# etch.net
KiCad netlist of a schematic drawn in EAGLE
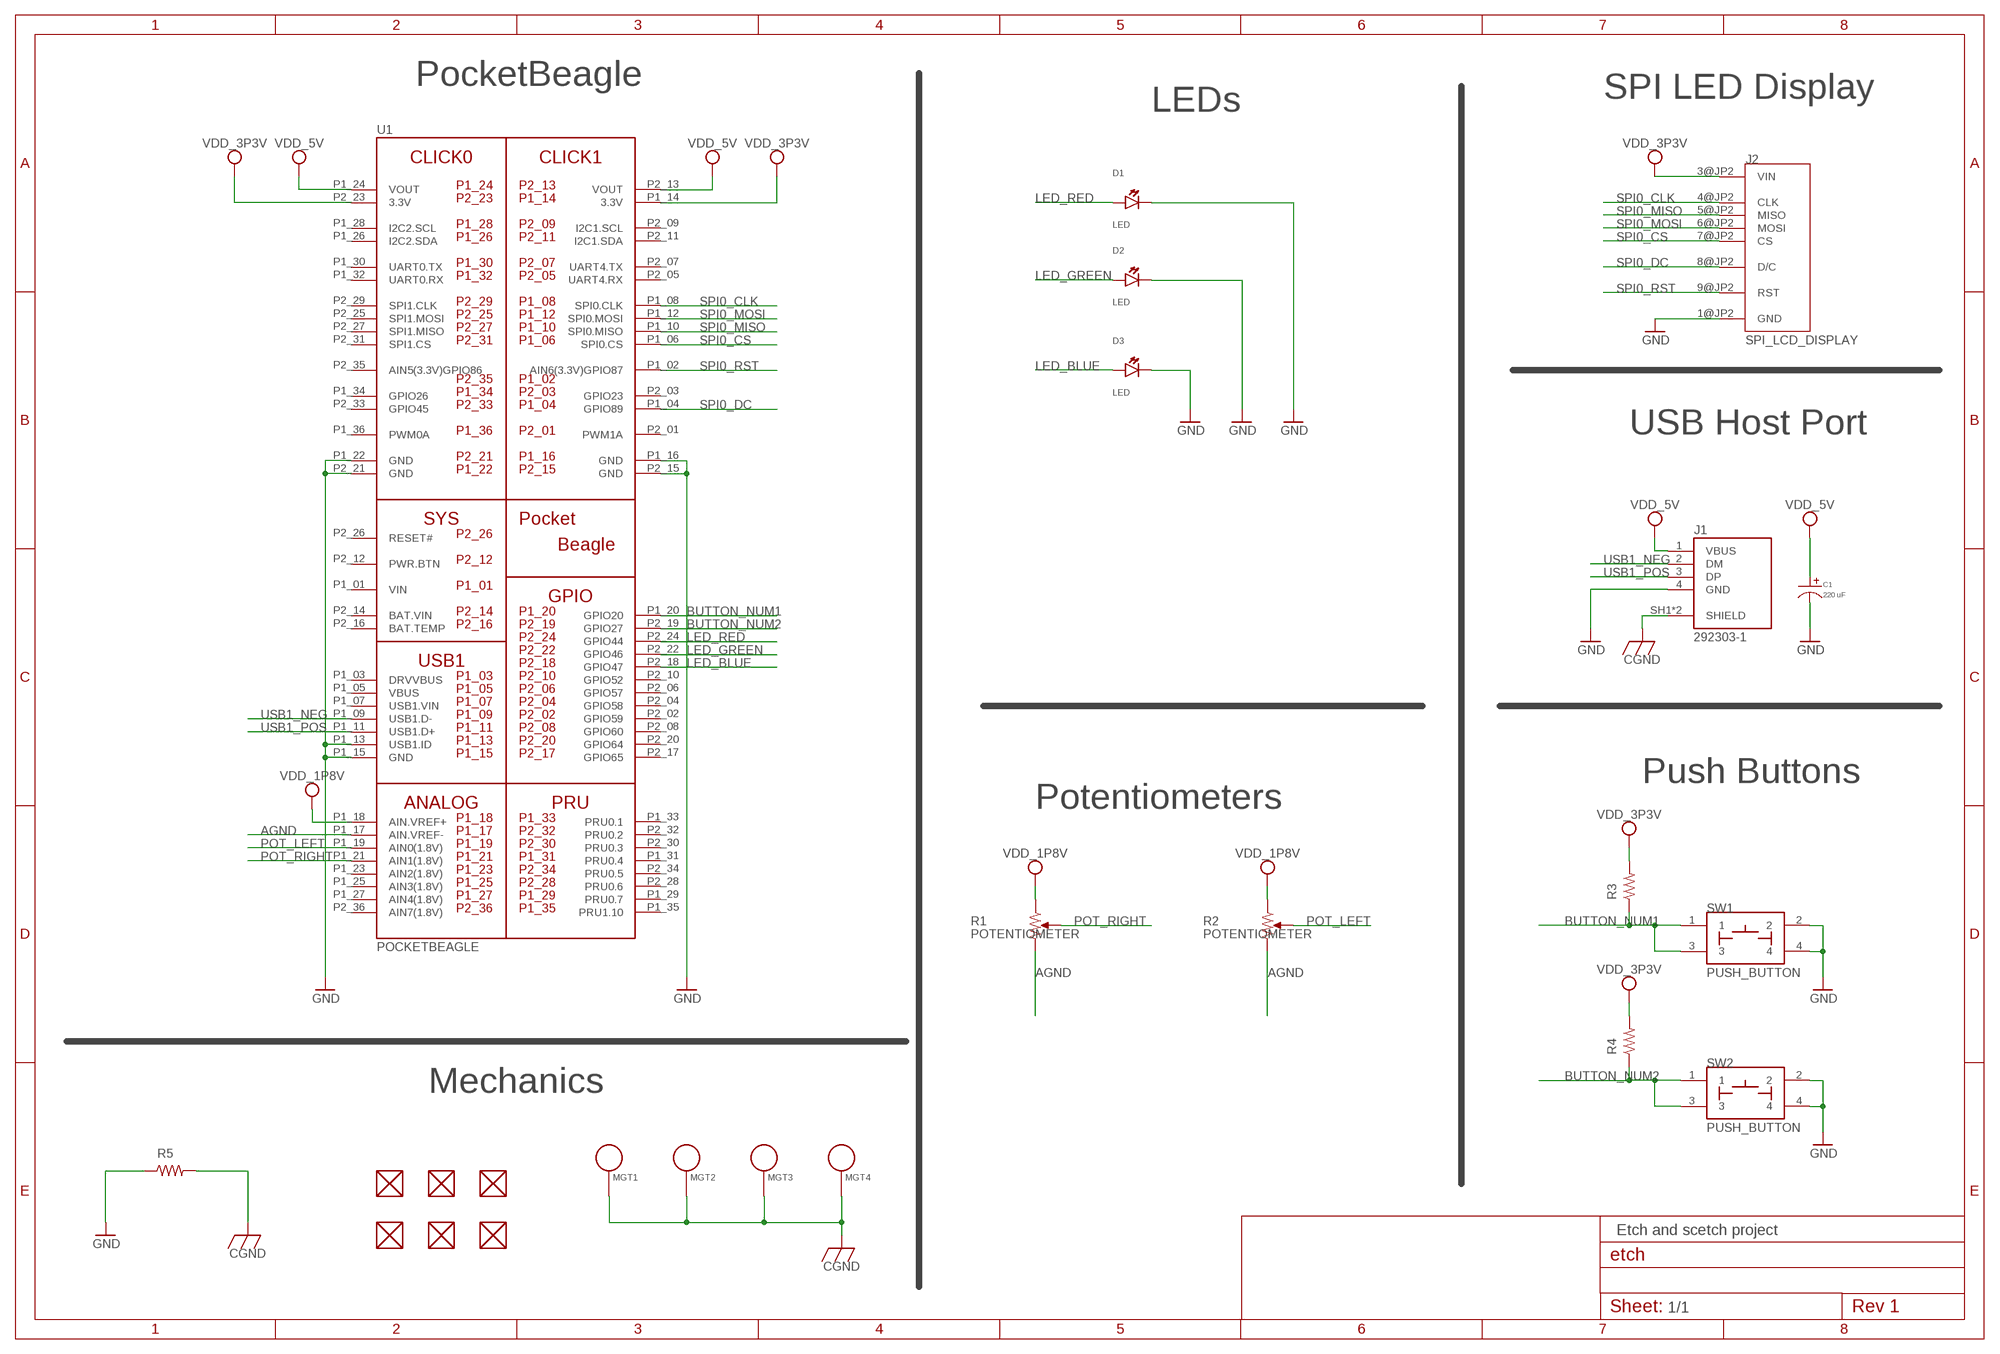
[diagram p0: schematic, sheet 1]

(export (version "E")
  (design (tool "Eeschema 10.0.6"))
  (components
    (comp (ref "C1")
      (value "220 uF")
      (footprint "eagle-import:CP10MM")
      (libsource (lib "eagle-import") (part "CAPACITOR_P_10MM"))
    )
    (comp (ref "D1")
      (value "LED")
      (footprint "eagle-import:EIA-STD")
      (libsource (lib "eagle-import") (part "LED"))
    )
    (comp (ref "D2")
      (value "LED")
      (footprint "eagle-import:EIA-STD")
      (libsource (lib "eagle-import") (part "LED"))
    )
    (comp (ref "D3")
      (value "LED")
      (footprint "eagle-import:EIA-STD")
      (libsource (lib "eagle-import") (part "LED"))
    )
    (comp (ref "FUD1")
      (value "FIDUCIAL")
      (footprint "eagle-import:FIDUCIAL_40MIL")
      (libsource (lib "eagle-import") (part "FIDUCIAL"))
    )
    (comp (ref "FUD2")
      (value "FIDUCIAL")
      (footprint "eagle-import:FIDUCIAL_40MIL")
      (libsource (lib "eagle-import") (part "FIDUCIAL"))
    )
    (comp (ref "FUD3")
      (value "FIDUCIAL")
      (footprint "eagle-import:FIDUCIAL_40MIL")
      (libsource (lib "eagle-import") (part "FIDUCIAL"))
    )
    (comp (ref "FUD4")
      (value "FIDUCIAL")
      (footprint "eagle-import:FIDUCIAL_40MIL")
      (libsource (lib "eagle-import") (part "FIDUCIAL"))
    )
    (comp (ref "FUD5")
      (value "FIDUCIAL")
      (footprint "eagle-import:FIDUCIAL_40MIL")
      (libsource (lib "eagle-import") (part "FIDUCIAL"))
    )
    (comp (ref "FUD6")
      (value "FIDUCIAL")
      (footprint "eagle-import:FIDUCIAL_40MIL")
      (libsource (lib "eagle-import") (part "FIDUCIAL"))
    )
    (comp (ref "J1")
      (value "292303-1")
      (footprint "eagle-import:TE_292303-1")
      (fields (field (name "MF") "TE Connectivity"))
      (libsource (lib "eagle-import") (part "292303-1"))
    )
    (comp (ref "J2")
      (value "SPI_LCD_DISPLAY")
      (footprint "eagle-import:TFT_LCD_PCB")
      (libsource (lib "eagle-import") (part "SPI_LCD_DISPLAY"))
    )
    (comp (ref "MGT1")
      (value "MOUNTING_HOLE")
      (footprint "eagle-import:MOUNTING_HOLE")
      (libsource (lib "eagle-import") (part "MOUNTING_HOLE"))
    )
    (comp (ref "MGT2")
      (value "MOUNTING_HOLE")
      (footprint "eagle-import:MOUNTING_HOLE")
      (libsource (lib "eagle-import") (part "MOUNTING_HOLE"))
    )
    (comp (ref "MGT3")
      (value "MOUNTING_HOLE")
      (footprint "eagle-import:MOUNTING_HOLE")
      (libsource (lib "eagle-import") (part "MOUNTING_HOLE"))
    )
    (comp (ref "MGT4")
      (value "MOUNTING_HOLE")
      (footprint "eagle-import:MOUNTING_HOLE")
      (libsource (lib "eagle-import") (part "MOUNTING_HOLE"))
    )
    (comp (ref "R1")
      (value "POTENTIOMETER")
      (footprint "eagle-import:POT-PO90S")
      (libsource (lib "eagle-import") (part "POTENTIOMETER"))
    )
    (comp (ref "R2")
      (value "POTENTIOMETER")
      (footprint "eagle-import:POT-PO90S")
      (libsource (lib "eagle-import") (part "POTENTIOMETER"))
    )
    (comp (ref "R3")
      (value "R_R0603")
      (footprint "eagle-import:R0603")
      (libsource (lib "eagle-import") (part "R_R0603"))
    )
    (comp (ref "R4")
      (value "R_R0603")
      (footprint "eagle-import:R0603")
      (libsource (lib "eagle-import") (part "R_R0603"))
    )
    (comp (ref "R5")
      (value "R_R0603")
      (footprint "eagle-import:R0603")
      (libsource (lib "eagle-import") (part "R_R0603"))
    )
    (comp (ref "SW1")
      (value "PUSH_BUTTON")
      (footprint "eagle-import:BUTTON_12.5MM")
      (libsource (lib "eagle-import") (part "PUSH_BUTTON"))
    )
    (comp (ref "SW2")
      (value "PUSH_BUTTON")
      (footprint "eagle-import:BUTTON_12.5MM")
      (libsource (lib "eagle-import") (part "PUSH_BUTTON"))
    )
    (comp (ref "U1")
      (value "POCKETBEAGLE")
      (footprint "eagle-import:POCKETBEAGLE")
      (libsource (lib "eagle-import") (part "POCKETBEAGLE"))
    )
  )
  (nets
    (net (code "1") (name "/AGND") (class "Default")
      (node (ref "R1") (pin "CW") (pinfunction "CW_CW") (pintype "passive"))
      (node (ref "R2") (pin "CW") (pinfunction "CW_CW") (pintype "passive"))
      (node (ref "U1") (pin "P1_17") (pinfunction "AIN.VREF-_P1_17") (pintype "input"))
    )
    (net (code "2") (name "/BAT.VIN") (class "Default")
      (node (ref "U1") (pin "P2_14") (pinfunction "BAT.VIN_P2_14") (pintype "power_in"))
    )
    (net (code "3") (name "/BUTTON_NUM1") (class "Default")
      (node (ref "R3") (pin "1") (pinfunction "1_1") (pintype "passive"))
      (node (ref "SW1") (pin "1") (pinfunction "1_1") (pintype "bidirectional"))
      (node (ref "SW1") (pin "3") (pinfunction "3_3") (pintype "bidirectional"))
      (node (ref "U1") (pin "P1_20") (pinfunction "GPIO20_P1_20") (pintype "bidirectional"))
    )
    (net (code "4") (name "/BUTTON_NUM2") (class "Default")
      (node (ref "R4") (pin "1") (pinfunction "1_1") (pintype "passive"))
      (node (ref "SW2") (pin "1") (pinfunction "1_1") (pintype "bidirectional"))
      (node (ref "SW2") (pin "3") (pinfunction "3_3") (pintype "bidirectional"))
      (node (ref "U1") (pin "P2_19") (pinfunction "GPIO27_P2_19") (pintype "bidirectional"))
    )
    (net (code "5") (name "/LED_BLUE") (class "Default")
      (node (ref "D3") (pin "ANODE") (pinfunction "ANODE_ANODE") (pintype "bidirectional"))
      (node (ref "U1") (pin "P2_18") (pinfunction "GPIO47_P2_18") (pintype "bidirectional"))
    )
    (net (code "6") (name "/LED_GREEN") (class "Default")
      (node (ref "D2") (pin "ANODE") (pinfunction "ANODE_ANODE") (pintype "bidirectional"))
      (node (ref "U1") (pin "P2_22") (pinfunction "GPIO46_P2_22") (pintype "bidirectional"))
    )
    (net (code "7") (name "/LED_RED") (class "Default")
      (node (ref "D1") (pin "ANODE") (pinfunction "ANODE_ANODE") (pintype "bidirectional"))
      (node (ref "U1") (pin "P2_24") (pinfunction "GPIO44_P2_24") (pintype "bidirectional"))
    )
    (net (code "8") (name "/POT_LEFT") (class "Default")
      (node (ref "R2") (pin "S") (pinfunction "S_S") (pintype "bidirectional"))
      (node (ref "U1") (pin "P1_19") (pinfunction "AIN0(1.8V)_P1_19") (pintype "input"))
    )
    (net (code "9") (name "/POT_RIGHT") (class "Default")
      (node (ref "R1") (pin "S") (pinfunction "S_S") (pintype "bidirectional"))
      (node (ref "U1") (pin "P1_21") (pinfunction "AIN1(1.8V)_P1_21") (pintype "input"))
    )
    (net (code "10") (name "/SPI0_CLK") (class "Default")
      (node (ref "J2") (pin "4@JP2") (pinfunction "CLK_4@JP2") (pintype "bidirectional"))
      (node (ref "U1") (pin "P1_08") (pinfunction "SPI0.CLK_P1_08") (pintype "bidirectional"))
    )
    (net (code "11") (name "/SPI0_CS") (class "Default")
      (node (ref "J2") (pin "7@JP2") (pinfunction "CS_7@JP2") (pintype "bidirectional"))
      (node (ref "U1") (pin "P1_06") (pinfunction "SPI0.CS_P1_06") (pintype "bidirectional"))
    )
    (net (code "12") (name "/SPI0_DC") (class "Default")
      (node (ref "J2") (pin "8@JP2") (pinfunction "D/C_8@JP2") (pintype "bidirectional"))
      (node (ref "U1") (pin "P1_04") (pinfunction "GPIO89_P1_04") (pintype "bidirectional"))
    )
    (net (code "13") (name "/SPI0_MISO") (class "Default")
      (node (ref "J2") (pin "5@JP2") (pinfunction "MISO_5@JP2") (pintype "bidirectional"))
      (node (ref "U1") (pin "P1_10") (pinfunction "SPI0.MISO_P1_10") (pintype "bidirectional"))
    )
    (net (code "14") (name "/SPI0_MOSI") (class "Default")
      (node (ref "J2") (pin "6@JP2") (pinfunction "MOSI_6@JP2") (pintype "bidirectional"))
      (node (ref "U1") (pin "P1_12") (pinfunction "SPI0.MOSI_P1_12") (pintype "bidirectional"))
    )
    (net (code "15") (name "/SPI0_RST") (class "Default")
      (node (ref "J2") (pin "9@JP2") (pinfunction "RST_9@JP2") (pintype "bidirectional"))
      (node (ref "U1") (pin "P1_02") (pinfunction "AIN6(3.3V)GPIO87_P1_02") (pintype "bidirectional"))
    )
    (net (code "16") (name "/USB1_NEG") (class "Default")
      (node (ref "J1") (pin "2") (pinfunction "DM_2") (pintype "passive"))
      (node (ref "U1") (pin "P1_09") (pinfunction "USB1.D-_P1_09") (pintype "bidirectional"))
    )
    (net (code "17") (name "/USB1_POS") (class "Default")
      (node (ref "J1") (pin "3") (pinfunction "DP_3") (pintype "passive"))
      (node (ref "U1") (pin "P1_11") (pinfunction "USB1.D+_P1_11") (pintype "bidirectional"))
    )
    (net (code "18") (name "/VIN") (class "Default")
      (node (ref "U1") (pin "P1_01") (pinfunction "VIN_P1_01") (pintype "power_in"))
    )
    (net (code "19") (name "CGND") (class "Default")
      (node (ref "J1") (pin "SH1") (pinfunction "SHIELD_SH1") (pintype "passive"))
      (node (ref "J1") (pin "SH2") (pinfunction "SHIELD_SH2") (pintype "passive"))
      (node (ref "MGT1") (pin "P$1") (pinfunction "P$1_P$1") (pintype "bidirectional"))
      (node (ref "MGT2") (pin "P$1") (pinfunction "P$1_P$1") (pintype "bidirectional"))
      (node (ref "MGT3") (pin "P$1") (pinfunction "P$1_P$1") (pintype "bidirectional"))
      (node (ref "MGT4") (pin "P$1") (pinfunction "P$1_P$1") (pintype "bidirectional"))
      (node (ref "R5") (pin "2") (pinfunction "2_2") (pintype "passive"))
    )
    (net (code "20") (name "GND") (class "Default")
      (node (ref "C1") (pin "P$2") (pinfunction "P$2_P$2") (pintype "passive"))
      (node (ref "D1") (pin "CATHODE") (pinfunction "CATHODE_CATHODE") (pintype "bidirectional"))
      (node (ref "D2") (pin "CATHODE") (pinfunction "CATHODE_CATHODE") (pintype "bidirectional"))
      (node (ref "D3") (pin "CATHODE") (pinfunction "CATHODE_CATHODE") (pintype "bidirectional"))
      (node (ref "J1") (pin "4") (pinfunction "GND_4") (pintype "passive"))
      (node (ref "J2") (pin "1@JP2") (pinfunction "GND_1@JP2") (pintype "bidirectional"))
      (node (ref "R5") (pin "1") (pinfunction "1_1") (pintype "passive"))
      (node (ref "SW1") (pin "2") (pinfunction "2_2") (pintype "bidirectional"))
      (node (ref "SW1") (pin "4") (pinfunction "4_4") (pintype "bidirectional"))
      (node (ref "SW2") (pin "2") (pinfunction "2_2") (pintype "bidirectional"))
      (node (ref "SW2") (pin "4") (pinfunction "4_4") (pintype "bidirectional"))
      (node (ref "U1") (pin "P1_13") (pinfunction "USB1.ID_P1_13") (pintype "bidirectional"))
      (node (ref "U1") (pin "P1_15") (pinfunction "GND_P1_15") (pintype "bidirectional"))
      (node (ref "U1") (pin "P1_16") (pinfunction "GND_P1_16") (pintype "power_in"))
      (node (ref "U1") (pin "P1_22") (pinfunction "GND_P1_22") (pintype "power_in"))
      (node (ref "U1") (pin "P2_15") (pinfunction "GND_P2_15") (pintype "power_in"))
      (node (ref "U1") (pin "P2_21") (pinfunction "GND_P2_21") (pintype "power_in"))
    )
    (net (code "21") (name "VDD_1P8V") (class "Default")
      (node (ref "R1") (pin "CCW") (pinfunction "CCW_CCW") (pintype "passive"))
      (node (ref "R2") (pin "CCW") (pinfunction "CCW_CCW") (pintype "passive"))
      (node (ref "U1") (pin "P1_18") (pinfunction "AIN.VREF+_P1_18") (pintype "input"))
    )
    (net (code "22") (name "VDD_3P3V") (class "Default")
      (node (ref "J2") (pin "3@JP2") (pinfunction "VIN_3@JP2") (pintype "bidirectional"))
      (node (ref "R3") (pin "2") (pinfunction "2_2") (pintype "passive"))
      (node (ref "R4") (pin "2") (pinfunction "2_2") (pintype "passive"))
      (node (ref "U1") (pin "P1_14") (pinfunction "3.3V_P1_14") (pintype "power_in"))
      (node (ref "U1") (pin "P2_23") (pinfunction "3.3V_P2_23") (pintype "power_in"))
    )
    (net (code "23") (name "VDD_5V") (class "Default")
      (node (ref "C1") (pin "P$1") (pinfunction "P$1_P$1") (pintype "passive"))
      (node (ref "J1") (pin "1") (pinfunction "VBUS_1") (pintype "passive"))
      (node (ref "U1") (pin "P1_24") (pinfunction "VOUT_P1_24") (pintype "power_in"))
      (node (ref "U1") (pin "P2_13") (pinfunction "VOUT_P2_13") (pintype "power_in"))
    )
    (net (code "24") (name "unconnected-(FUD1-PadP$1)") (class "Default")
      (node (ref "FUD1") (pin "P$1") (pinfunction "P$1_P$1") (pintype "no_connect"))
    )
    (net (code "25") (name "unconnected-(FUD2-PadP$1)") (class "Default")
      (node (ref "FUD2") (pin "P$1") (pinfunction "P$1_P$1") (pintype "no_connect"))
    )
    (net (code "26") (name "unconnected-(FUD3-PadP$1)") (class "Default")
      (node (ref "FUD3") (pin "P$1") (pinfunction "P$1_P$1") (pintype "no_connect"))
    )
    (net (code "27") (name "unconnected-(FUD4-PadP$1)") (class "Default")
      (node (ref "FUD4") (pin "P$1") (pinfunction "P$1_P$1") (pintype "no_connect"))
    )
    (net (code "28") (name "unconnected-(FUD5-PadP$1)") (class "Default")
      (node (ref "FUD5") (pin "P$1") (pinfunction "P$1_P$1") (pintype "no_connect"))
    )
    (net (code "29") (name "unconnected-(FUD6-PadP$1)") (class "Default")
      (node (ref "FUD6") (pin "P$1") (pinfunction "P$1_P$1") (pintype "no_connect"))
    )
    (net (code "30") (name "unconnected-(U1-AIN2(1.8V)-PadP1_23)") (class "Default")
      (node (ref "U1") (pin "P1_23") (pinfunction "AIN2(1.8V)_P1_23") (pintype "input"))
    )
    (net (code "31") (name "unconnected-(U1-AIN3(1.8V)-PadP1_25)") (class "Default")
      (node (ref "U1") (pin "P1_25") (pinfunction "AIN3(1.8V)_P1_25") (pintype "input"))
    )
    (net (code "32") (name "unconnected-(U1-AIN4(1.8V)-PadP1_27)") (class "Default")
      (node (ref "U1") (pin "P1_27") (pinfunction "AIN4(1.8V)_P1_27") (pintype "input"))
    )
    (net (code "33") (name "unconnected-(U1-AIN5(3.3V)GPIO86-PadP2_35)") (class "Default")
      (node (ref "U1") (pin "P2_35") (pinfunction "AIN5(3.3V)GPIO86_P2_35") (pintype "bidirectional"))
    )
    (net (code "34") (name "unconnected-(U1-AIN7(1.8V)-PadP2_36)") (class "Default")
      (node (ref "U1") (pin "P2_36") (pinfunction "AIN7(1.8V)_P2_36") (pintype "input"))
    )
    (net (code "35") (name "unconnected-(U1-BAT.TEMP-PadP2_16)") (class "Default")
      (node (ref "U1") (pin "P2_16") (pinfunction "BAT.TEMP_P2_16") (pintype "input"))
    )
    (net (code "36") (name "unconnected-(U1-DRVVBUS-PadP1_03)") (class "Default")
      (node (ref "U1") (pin "P1_03") (pinfunction "DRVVBUS_P1_03") (pintype "bidirectional"))
    )
    (net (code "37") (name "unconnected-(U1-GPIO23-PadP2_03)") (class "Default")
      (node (ref "U1") (pin "P2_03") (pinfunction "GPIO23_P2_03") (pintype "bidirectional"))
    )
    (net (code "38") (name "unconnected-(U1-GPIO26-PadP1_34)") (class "Default")
      (node (ref "U1") (pin "P1_34") (pinfunction "GPIO26_P1_34") (pintype "bidirectional"))
    )
    (net (code "39") (name "unconnected-(U1-GPIO45-PadP2_33)") (class "Default")
      (node (ref "U1") (pin "P2_33") (pinfunction "GPIO45_P2_33") (pintype "bidirectional"))
    )
    (net (code "40") (name "unconnected-(U1-GPIO52-PadP2_10)") (class "Default")
      (node (ref "U1") (pin "P2_10") (pinfunction "GPIO52_P2_10") (pintype "bidirectional"))
    )
    (net (code "41") (name "unconnected-(U1-GPIO57-PadP2_06)") (class "Default")
      (node (ref "U1") (pin "P2_06") (pinfunction "GPIO57_P2_06") (pintype "bidirectional"))
    )
    (net (code "42") (name "unconnected-(U1-GPIO58-PadP2_04)") (class "Default")
      (node (ref "U1") (pin "P2_04") (pinfunction "GPIO58_P2_04") (pintype "bidirectional"))
    )
    (net (code "43") (name "unconnected-(U1-GPIO59-PadP2_02)") (class "Default")
      (node (ref "U1") (pin "P2_02") (pinfunction "GPIO59_P2_02") (pintype "bidirectional"))
    )
    (net (code "44") (name "unconnected-(U1-GPIO60-PadP2_08)") (class "Default")
      (node (ref "U1") (pin "P2_08") (pinfunction "GPIO60_P2_08") (pintype "bidirectional"))
    )
    (net (code "45") (name "unconnected-(U1-GPIO64-PadP2_20)") (class "Default")
      (node (ref "U1") (pin "P2_20") (pinfunction "GPIO64_P2_20") (pintype "bidirectional"))
    )
    (net (code "46") (name "unconnected-(U1-GPIO65-PadP2_17)") (class "Default")
      (node (ref "U1") (pin "P2_17") (pinfunction "GPIO65_P2_17") (pintype "bidirectional"))
    )
    (net (code "47") (name "unconnected-(U1-I2C1.SCL-PadP2_09)") (class "Default")
      (node (ref "U1") (pin "P2_09") (pinfunction "I2C1.SCL_P2_09") (pintype "bidirectional"))
    )
    (net (code "48") (name "unconnected-(U1-I2C1.SDA-PadP2_11)") (class "Default")
      (node (ref "U1") (pin "P2_11") (pinfunction "I2C1.SDA_P2_11") (pintype "bidirectional"))
    )
    (net (code "49") (name "unconnected-(U1-I2C2.SCL-PadP1_28)") (class "Default")
      (node (ref "U1") (pin "P1_28") (pinfunction "I2C2.SCL_P1_28") (pintype "bidirectional"))
    )
    (net (code "50") (name "unconnected-(U1-I2C2.SDA-PadP1_26)") (class "Default")
      (node (ref "U1") (pin "P1_26") (pinfunction "I2C2.SDA_P1_26") (pintype "bidirectional"))
    )
    (net (code "51") (name "unconnected-(U1-PRU0.1-PadP1_33)") (class "Default")
      (node (ref "U1") (pin "P1_33") (pinfunction "PRU0.1_P1_33") (pintype "bidirectional"))
    )
    (net (code "52") (name "unconnected-(U1-PRU0.2-PadP2_32)") (class "Default")
      (node (ref "U1") (pin "P2_32") (pinfunction "PRU0.2_P2_32") (pintype "bidirectional"))
    )
    (net (code "53") (name "unconnected-(U1-PRU0.3-PadP2_30)") (class "Default")
      (node (ref "U1") (pin "P2_30") (pinfunction "PRU0.3_P2_30") (pintype "bidirectional"))
    )
    (net (code "54") (name "unconnected-(U1-PRU0.4-PadP1_31)") (class "Default")
      (node (ref "U1") (pin "P1_31") (pinfunction "PRU0.4_P1_31") (pintype "bidirectional"))
    )
    (net (code "55") (name "unconnected-(U1-PRU0.5-PadP2_34)") (class "Default")
      (node (ref "U1") (pin "P2_34") (pinfunction "PRU0.5_P2_34") (pintype "bidirectional"))
    )
    (net (code "56") (name "unconnected-(U1-PRU0.6-PadP2_28)") (class "Default")
      (node (ref "U1") (pin "P2_28") (pinfunction "PRU0.6_P2_28") (pintype "bidirectional"))
    )
    (net (code "57") (name "unconnected-(U1-PRU0.7-PadP1_29)") (class "Default")
      (node (ref "U1") (pin "P1_29") (pinfunction "PRU0.7_P1_29") (pintype "bidirectional"))
    )
    (net (code "58") (name "unconnected-(U1-PRU1.10-PadP1_35)") (class "Default")
      (node (ref "U1") (pin "P1_35") (pinfunction "PRU1.10_P1_35") (pintype "bidirectional"))
    )
    (net (code "59") (name "unconnected-(U1-PWM0A-PadP1_36)") (class "Default")
      (node (ref "U1") (pin "P1_36") (pinfunction "PWM0A_P1_36") (pintype "bidirectional"))
    )
    (net (code "60") (name "unconnected-(U1-PWM1A-PadP2_01)") (class "Default")
      (node (ref "U1") (pin "P2_01") (pinfunction "PWM1A_P2_01") (pintype "bidirectional"))
    )
    (net (code "61") (name "unconnected-(U1-PWR.BTN-PadP2_12)") (class "Default")
      (node (ref "U1") (pin "P2_12") (pinfunction "PWR.BTN_P2_12") (pintype "input"))
    )
    (net (code "62") (name "unconnected-(U1-RESET#-PadP2_26)") (class "Default")
      (node (ref "U1") (pin "P2_26") (pinfunction "RESET#_P2_26") (pintype "input"))
    )
    (net (code "63") (name "unconnected-(U1-SPI1.CLK-PadP2_29)") (class "Default")
      (node (ref "U1") (pin "P2_29") (pinfunction "SPI1.CLK_P2_29") (pintype "bidirectional"))
    )
    (net (code "64") (name "unconnected-(U1-SPI1.CS-PadP2_31)") (class "Default")
      (node (ref "U1") (pin "P2_31") (pinfunction "SPI1.CS_P2_31") (pintype "bidirectional"))
    )
    (net (code "65") (name "unconnected-(U1-SPI1.MISO-PadP2_27)") (class "Default")
      (node (ref "U1") (pin "P2_27") (pinfunction "SPI1.MISO_P2_27") (pintype "bidirectional"))
    )
    (net (code "66") (name "unconnected-(U1-SPI1.MOSI-PadP2_25)") (class "Default")
      (node (ref "U1") (pin "P2_25") (pinfunction "SPI1.MOSI_P2_25") (pintype "bidirectional"))
    )
    (net (code "67") (name "unconnected-(U1-UART0.RX-PadP1_32)") (class "Default")
      (node (ref "U1") (pin "P1_32") (pinfunction "UART0.RX_P1_32") (pintype "bidirectional"))
    )
    (net (code "68") (name "unconnected-(U1-UART0.TX-PadP1_30)") (class "Default")
      (node (ref "U1") (pin "P1_30") (pinfunction "UART0.TX_P1_30") (pintype "bidirectional"))
    )
    (net (code "69") (name "unconnected-(U1-UART4.RX-PadP2_05)") (class "Default")
      (node (ref "U1") (pin "P2_05") (pinfunction "UART4.RX_P2_05") (pintype "bidirectional"))
    )
    (net (code "70") (name "unconnected-(U1-UART4.TX-PadP2_07)") (class "Default")
      (node (ref "U1") (pin "P2_07") (pinfunction "UART4.TX_P2_07") (pintype "bidirectional"))
    )
    (net (code "71") (name "unconnected-(U1-USB1.VIN-PadP1_07)") (class "Default")
      (node (ref "U1") (pin "P1_07") (pinfunction "USB1.VIN_P1_07") (pintype "bidirectional"))
    )
    (net (code "72") (name "unconnected-(U1-VBUS-PadP1_05)") (class "Default")
      (node (ref "U1") (pin "P1_05") (pinfunction "VBUS_P1_05") (pintype "bidirectional"))
    )
  )
)
